# Isolator.net
KiCad netlist of a schematic drawn in Altium Designer
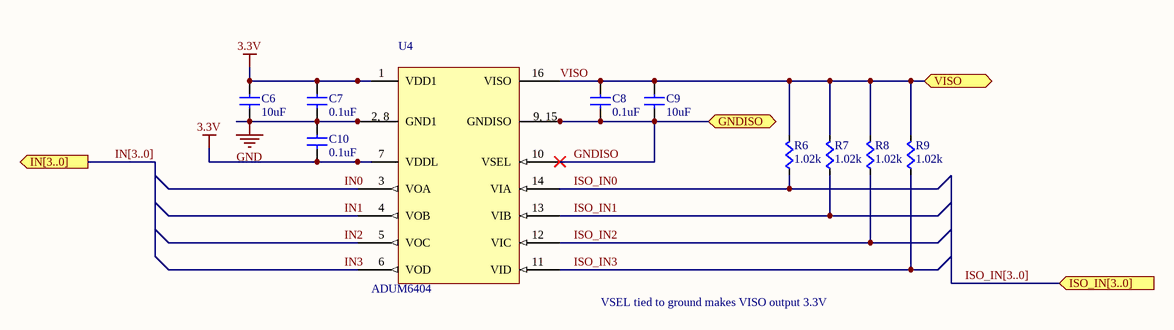
[diagram p0: Isolator.SchDoc]

(export (version "E")
  (design (tool "Eeschema 10.0.6"))
  (components
    (comp (ref "C6")
      (value "10uF")
      (footprint "CAPC0603")
      (fields (field (name "Comment") "Cap"))
      (libsource (lib "Passives") (part "Cap"))
    )
    (comp (ref "C7")
      (value "0.1uF")
      (footprint "CAPC0603")
      (fields (field (name "Comment") "Cap"))
      (libsource (lib "Passives") (part "Cap"))
    )
    (comp (ref "C8")
      (value "0.1uF")
      (footprint "CAPC0603")
      (fields (field (name "Comment") "Cap"))
      (libsource (lib "Passives") (part "Cap"))
    )
    (comp (ref "C9")
      (value "10uF")
      (footprint "CAPC0603")
      (fields (field (name "Comment") "Cap"))
      (libsource (lib "Passives") (part "Cap"))
    )
    (comp (ref "C10")
      (value "0.1uF")
      (footprint "CAPC0603")
      (fields (field (name "Comment") "Cap"))
      (libsource (lib "Passives") (part "Cap"))
    )
    (comp (ref "R6")
      (value "1.02k")
      (footprint "RES0603")
      (fields (field (name "Comment") "Res"))
      (libsource (lib "Passives") (part "Res"))
    )
    (comp (ref "R7")
      (value "1.02k")
      (footprint "RES0603")
      (fields (field (name "Comment") "Res"))
      (libsource (lib "Passives") (part "Res"))
    )
    (comp (ref "R8")
      (value "1.02k")
      (footprint "RES0603")
      (fields (field (name "Comment") "Res"))
      (libsource (lib "Passives") (part "Res"))
    )
    (comp (ref "R9")
      (value "1.02k")
      (footprint "RES0603")
      (fields (field (name "Comment") "Res"))
      (libsource (lib "Passives") (part "Res"))
    )
    (comp (ref "U4")
      (value "ADUM6404")
      (footprint "SOIC127P1030X265-16N")
      (description "Digital Isolator, 4 channel, with isolated power")
      (libsource (lib "ICs") (part "ADUM6404"))
    )
  )
  (nets
    (net (code "1") (name "/GNDISO") (class "Default")
      (node (ref "C8") (pin "1") (pinfunction "A_1") (pintype "passive"))
      (node (ref "C9") (pin "1") (pinfunction "A_1") (pintype "passive"))
      (node (ref "U4") (pin "10") (pinfunction "VSEL_10") (pintype "input"))
      (node (ref "U4") (pin "15") (pinfunction "GNDISO_15") (pintype "power_in"))
      (node (ref "U4") (pin "9") (pinfunction "GNDISO_9") (pintype "power_in"))
    )
    (net (code "2") (name "/IN0") (class "Default")
      (node (ref "U4") (pin "3") (pinfunction "VOA_3") (pintype "output"))
    )
    (net (code "3") (name "/IN1") (class "Default")
      (node (ref "U4") (pin "4") (pinfunction "VOB_4") (pintype "output"))
    )
    (net (code "4") (name "/IN2") (class "Default")
      (node (ref "U4") (pin "5") (pinfunction "VOC_5") (pintype "output"))
    )
    (net (code "5") (name "/IN3") (class "Default")
      (node (ref "U4") (pin "6") (pinfunction "VOD_6") (pintype "output"))
    )
    (net (code "7") (name "/ISO_IN0") (class "Default")
      (node (ref "R6") (pin "2") (pinfunction "B_2") (pintype "passive"))
      (node (ref "U4") (pin "14") (pinfunction "VIA_14") (pintype "input"))
    )
    (net (code "8") (name "/ISO_IN1") (class "Default")
      (node (ref "R7") (pin "2") (pinfunction "B_2") (pintype "passive"))
      (node (ref "U4") (pin "13") (pinfunction "VIB_13") (pintype "input"))
    )
    (net (code "9") (name "/ISO_IN2") (class "Default")
      (node (ref "R8") (pin "2") (pinfunction "B_2") (pintype "passive"))
      (node (ref "U4") (pin "12") (pinfunction "VIC_12") (pintype "input"))
    )
    (net (code "10") (name "/ISO_IN3") (class "Default")
      (node (ref "R9") (pin "2") (pinfunction "B_2") (pintype "passive"))
      (node (ref "U4") (pin "11") (pinfunction "VID_11") (pintype "input"))
    )
    (net (code "12") (name "/VISO") (class "Default")
      (node (ref "C8") (pin "2") (pinfunction "B_2") (pintype "passive"))
      (node (ref "C9") (pin "2") (pinfunction "B_2") (pintype "passive"))
      (node (ref "R6") (pin "1") (pinfunction "A_1") (pintype "passive"))
      (node (ref "R7") (pin "1") (pinfunction "A_1") (pintype "passive"))
      (node (ref "R8") (pin "1") (pinfunction "A_1") (pintype "passive"))
      (node (ref "R9") (pin "1") (pinfunction "A_1") (pintype "passive"))
      (node (ref "U4") (pin "16") (pinfunction "VISO_16") (pintype "passive"))
    )
    (net (code "13") (name "3.3V") (class "Default")
      (node (ref "C10") (pin "1") (pinfunction "A_1") (pintype "passive"))
      (node (ref "C6") (pin "2") (pinfunction "B_2") (pintype "passive"))
      (node (ref "C7") (pin "2") (pinfunction "B_2") (pintype "passive"))
      (node (ref "U4") (pin "1") (pinfunction "VDD1_1") (pintype "power_in"))
      (node (ref "U4") (pin "7") (pinfunction "VDDL_7") (pintype "power_in"))
    )
    (net (code "14") (name "GND") (class "Default")
      (node (ref "C10") (pin "2") (pinfunction "B_2") (pintype "passive"))
      (node (ref "C6") (pin "1") (pinfunction "A_1") (pintype "passive"))
      (node (ref "C7") (pin "1") (pinfunction "A_1") (pintype "passive"))
      (node (ref "U4") (pin "2") (pinfunction "GND1_2") (pintype "power_in"))
      (node (ref "U4") (pin "8") (pinfunction "GND1_8") (pintype "power_in"))
    )
  )
)
